# Y-babies_ATtiny84_v07.net
KiCad netlist of a schematic drawn in EAGLE
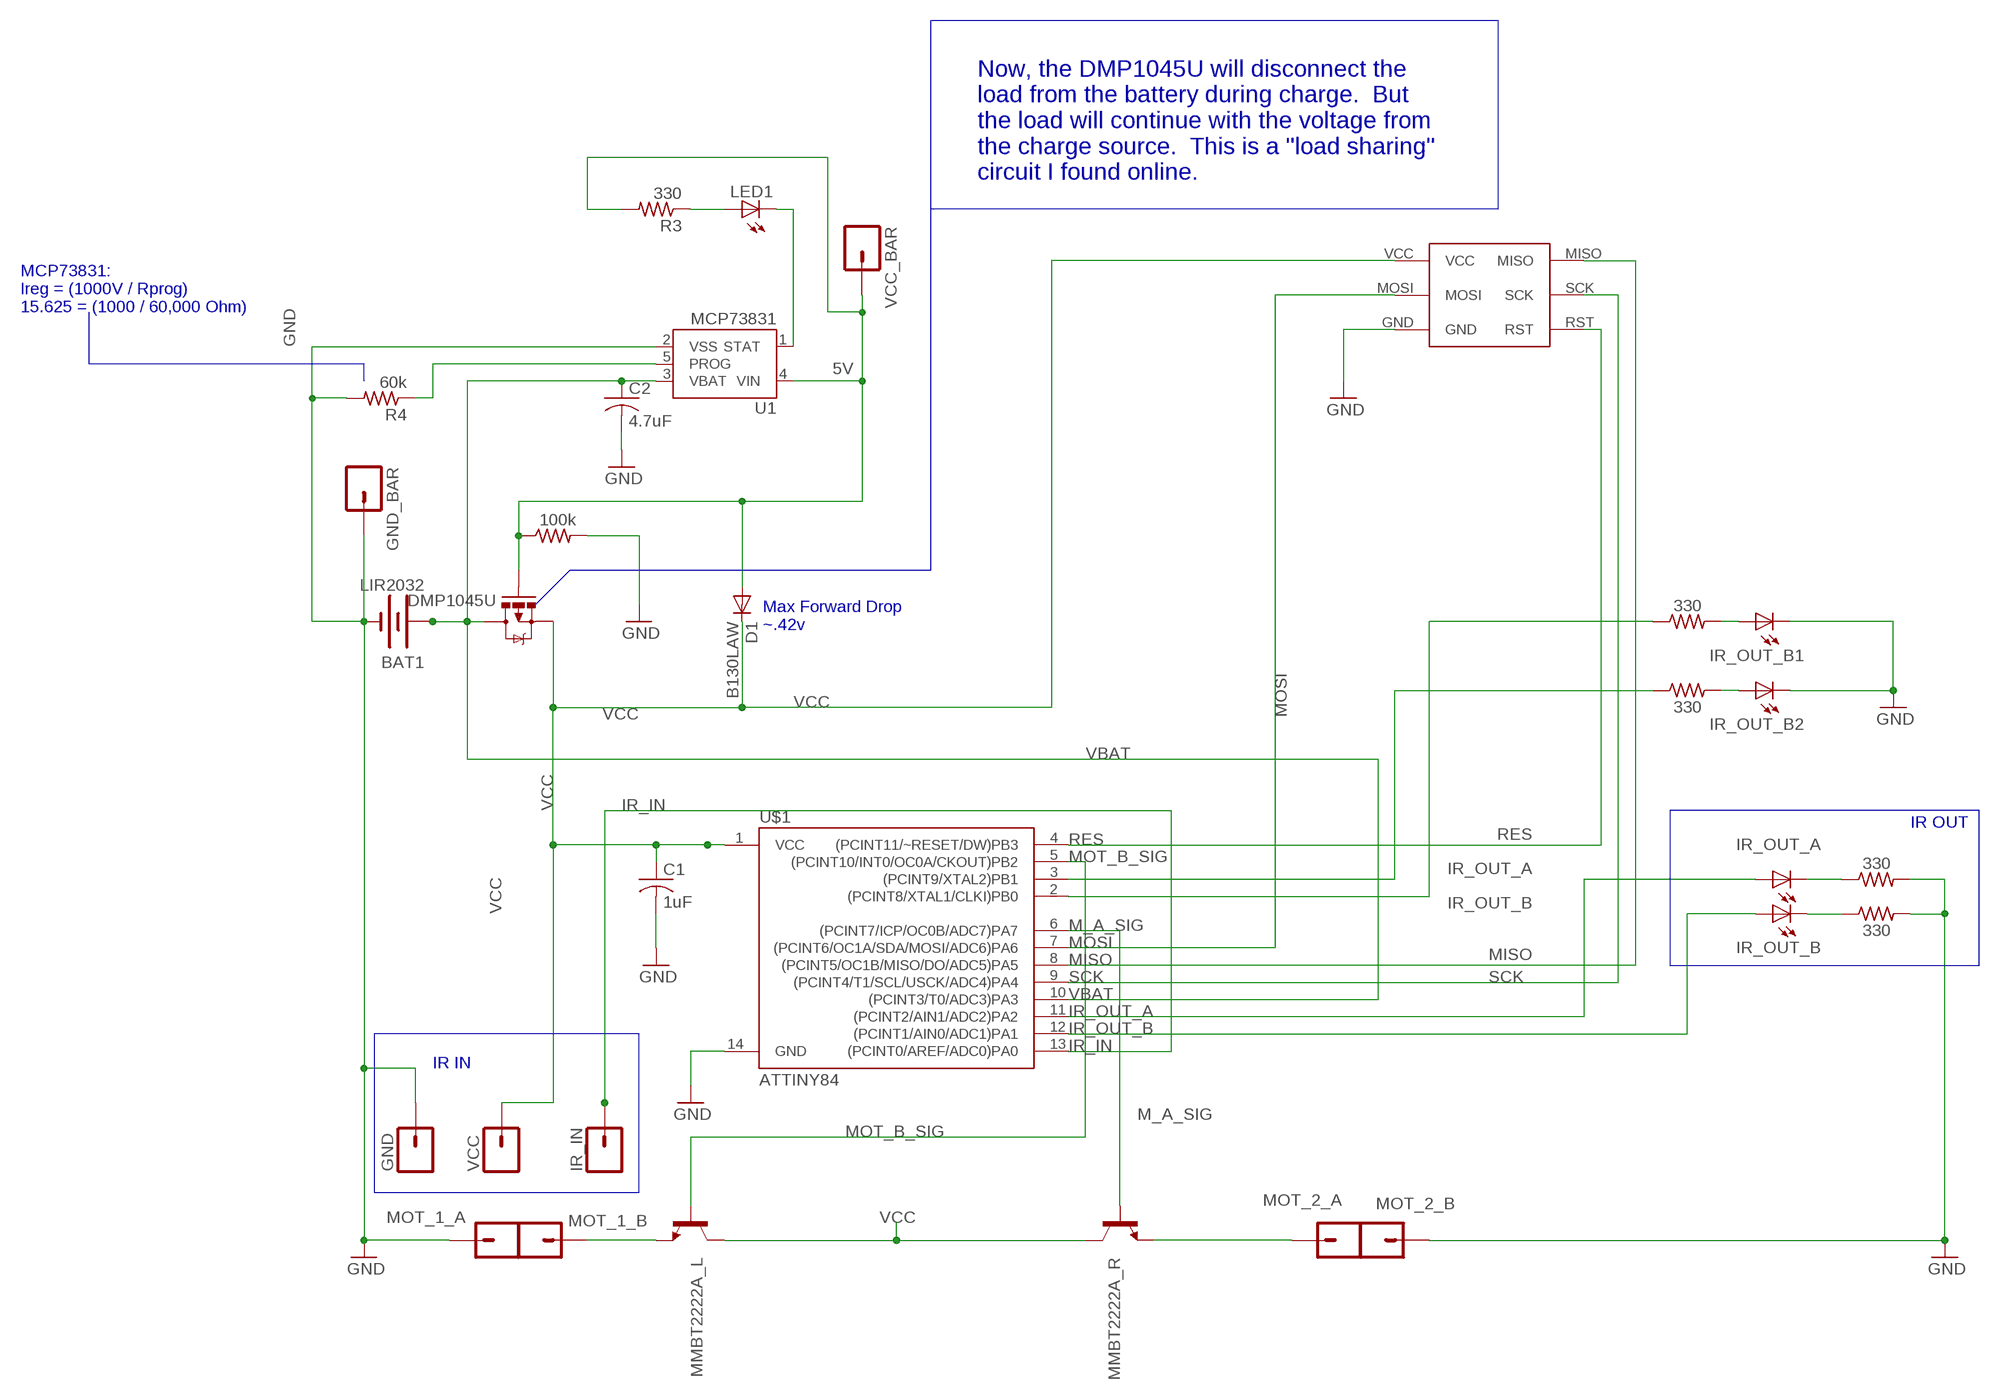
[diagram p0: schematic, sheet 1]

(export (version "E")
  (design (tool "Eeschema 10.0.6"))
  (components
    (comp (ref "BAT1")
      (value "LIR2032")
      (footprint "eagle-import:BATTCOM_20MM_PTH")
      (libsource (lib "eagle-import") (part "BATTERY20PTH"))
    )
    (comp (ref "C1")
      (value "1uF")
      (footprint "eagle-import:C0402K")
      (libsource (lib "eagle-import") (part "C-USC0402K"))
    )
    (comp (ref "C2")
      (value "4.7uF")
      (footprint "eagle-import:C0805K")
      (libsource (lib "eagle-import") (part "C-USC0805K"))
    )
    (comp (ref "D1")
      (value "B130LAW")
      (footprint "eagle-import:SOD123")
      (libsource (lib "eagle-import") (part "DIODE-SOD123"))
    )
    (comp (ref "DMP1045U")
      (value "MOSFET-PCHANNELSMD")
      (footprint "eagle-import:SOT23-3")
      (libsource (lib "eagle-import") (part "MOSFET-PCHANNELSMD"))
    )
    (comp (ref "GND")
      (value "M01PTH")
      (footprint "eagle-import:1X01")
      (libsource (lib "eagle-import") (part "M01PTH"))
    )
    (comp (ref "GND_BAR")
      (value "M01PTH")
      (footprint "eagle-import:1X01")
      (libsource (lib "eagle-import") (part "M01PTH"))
    )
    (comp (ref "IR_IN")
      (value "M01PTH")
      (footprint "eagle-import:1X01")
      (libsource (lib "eagle-import") (part "M01PTH"))
    )
    (comp (ref "IR_OUT_A")
      (value "LED3MM")
      (footprint "eagle-import:LED3MM")
      (libsource (lib "eagle-import") (part "LED3MM"))
    )
    (comp (ref "IR_OUT_B")
      (value "LED3MM")
      (footprint "eagle-import:LED3MM")
      (libsource (lib "eagle-import") (part "LED3MM"))
    )
    (comp (ref "IR_OUT_B1")
      (value "LEDSML0603")
      (footprint "eagle-import:SML0603")
      (libsource (lib "eagle-import") (part "LEDSML0603"))
    )
    (comp (ref "IR_OUT_B2")
      (value "LEDSML0603")
      (footprint "eagle-import:SML0603")
      (libsource (lib "eagle-import") (part "LEDSML0603"))
    )
    (comp (ref "LED1")
      (value "LEDSML0603")
      (footprint "eagle-import:SML0603")
      (libsource (lib "eagle-import") (part "LEDSML0603"))
    )
    (comp (ref "MMBT2222A_L")
      (value "TRANSISTOR_NPNSOT23")
      (footprint "eagle-import:SOT23")
      (libsource (lib "eagle-import") (part "TRANSISTOR_NPNSOT23"))
    )
    (comp (ref "MMBT2222A_R")
      (value "TRANSISTOR_NPNSOT23")
      (footprint "eagle-import:SOT23")
      (libsource (lib "eagle-import") (part "TRANSISTOR_NPNSOT23"))
    )
    (comp (ref "MOT_1_A")
      (value "M01SMD-4.5X1.5")
      (footprint "eagle-import:PAD-1.5X4.5")
      (libsource (lib "eagle-import") (part "M01SMD-4.5X1.5"))
    )
    (comp (ref "MOT_1_B")
      (value "M01SMD-4.5X1.5")
      (footprint "eagle-import:PAD-1.5X4.5")
      (libsource (lib "eagle-import") (part "M01SMD-4.5X1.5"))
    )
    (comp (ref "MOT_2_A")
      (value "M01SMD-4.5X1.5")
      (footprint "eagle-import:PAD-1.5X4.5")
      (libsource (lib "eagle-import") (part "M01SMD-4.5X1.5"))
    )
    (comp (ref "MOT_2_B")
      (value "M01SMD-4.5X1.5")
      (footprint "eagle-import:PAD-1.5X4.5")
      (libsource (lib "eagle-import") (part "M01SMD-4.5X1.5"))
    )
    (comp (ref "R1")
      (value "330")
      (footprint "eagle-import:R0402")
      (libsource (lib "eagle-import") (part "R-US_R0402"))
    )
    (comp (ref "R2")
      (value "330")
      (footprint "eagle-import:R0402")
      (libsource (lib "eagle-import") (part "R-US_R0402"))
    )
    (comp (ref "R3")
      (value "330")
      (footprint "eagle-import:R0402")
      (libsource (lib "eagle-import") (part "R-US_R0402"))
    )
    (comp (ref "R4")
      (value "60k")
      (footprint "eagle-import:R0402")
      (libsource (lib "eagle-import") (part "R-US_R0402"))
    )
    (comp (ref "R5")
      (value "100k")
      (footprint "eagle-import:R0402")
      (libsource (lib "eagle-import") (part "R-US_R0402"))
    )
    (comp (ref "R6")
      (value "330")
      (footprint "eagle-import:R0402")
      (libsource (lib "eagle-import") (part "R-US_R0402"))
    )
    (comp (ref "R7")
      (value "330")
      (footprint "eagle-import:R0402")
      (libsource (lib "eagle-import") (part "R-US_R0402"))
    )
    (comp (ref "U$1")
      (value "ATTINY84")
      (footprint "eagle-import:SO14")
      (libsource (lib "eagle-import") (part "ATTINY84"))
    )
    (comp (ref "U$2")
      (value "POGO_PIN_SPI_PAD")
      (footprint "eagle-import:POGO_PIN_SPI_PAD")
      (libsource (lib "eagle-import") (part "POGO_PIN_SPI_PAD"))
    )
    (comp (ref "U1")
      (value "MCP73831")
      (footprint "eagle-import:SOT23-5")
      (libsource (lib "eagle-import") (part "MCP73831"))
    )
    (comp (ref "VCC")
      (value "M01PTH")
      (footprint "eagle-import:1X01")
      (libsource (lib "eagle-import") (part "M01PTH"))
    )
    (comp (ref "VCC_BAR")
      (value "M01PTH")
      (footprint "eagle-import:1X01")
      (libsource (lib "eagle-import") (part "M01PTH"))
    )
  )
  (nets
    (net (code "1") (name "/5V") (class "Default")
      (node (ref "D1") (pin "A") (pinfunction "A_A") (pintype "passive"))
      (node (ref "DMP1045U") (pin "1") (pinfunction "G_1") (pintype "passive"))
      (node (ref "R3") (pin "2") (pinfunction "2_2") (pintype "passive"))
      (node (ref "R5") (pin "1") (pinfunction "1_1") (pintype "passive"))
      (node (ref "U1") (pin "4") (pinfunction "VIN_4") (pintype "power_in"))
      (node (ref "VCC_BAR") (pin "1") (pinfunction "1_1") (pintype "passive"))
    )
    (net (code "2") (name "/IR_IN") (class "Default")
      (node (ref "IR_IN") (pin "1") (pinfunction "1_1") (pintype "passive"))
      (node (ref "U$1") (pin "13") (pinfunction "(PCINT0/AREF/ADC0)PA0_13") (pintype "bidirectional"))
    )
    (net (code "3") (name "/IR_OUT_A") (class "Default")
      (node (ref "IR_OUT_A") (pin "A") (pinfunction "A_A") (pintype "passive"))
      (node (ref "U$1") (pin "11") (pinfunction "(PCINT2/AIN1/ADC2)PA2_11") (pintype "bidirectional"))
    )
    (net (code "4") (name "/IR_OUT_B") (class "Default")
      (node (ref "IR_OUT_B") (pin "A") (pinfunction "A_A") (pintype "passive"))
      (node (ref "U$1") (pin "12") (pinfunction "(PCINT1/AIN0/ADC1)PA1_12") (pintype "bidirectional"))
    )
    (net (code "5") (name "/MISO") (class "Default")
      (node (ref "U$1") (pin "8") (pinfunction "(PCINT5/OC1B/MISO/DO/ADC5)PA5_8") (pintype "bidirectional"))
      (node (ref "U$2") (pin "MISO") (pinfunction "MISO_MISO") (pintype "bidirectional"))
    )
    (net (code "6") (name "/MOSI") (class "Default")
      (node (ref "U$1") (pin "7") (pinfunction "(PCINT6/OC1A/SDA/MOSI/ADC6)PA6_7") (pintype "bidirectional"))
      (node (ref "U$2") (pin "MOSI") (pinfunction "MOSI_MOSI") (pintype "bidirectional"))
    )
    (net (code "7") (name "/MOT_B_SIG") (class "Default")
      (node (ref "MMBT2222A_L") (pin "1") (pinfunction "B_1") (pintype "passive"))
      (node (ref "U$1") (pin "5") (pinfunction "(PCINT10/INT0/OC0A/CKOUT)PB2_5") (pintype "bidirectional"))
    )
    (net (code "8") (name "/M_A_SIG") (class "Default")
      (node (ref "MMBT2222A_R") (pin "1") (pinfunction "B_1") (pintype "passive"))
      (node (ref "U$1") (pin "6") (pinfunction "(PCINT7/ICP/OC0B/ADC7)PA7_6") (pintype "bidirectional"))
    )
    (net (code "9") (name "/RES") (class "Default")
      (node (ref "U$1") (pin "4") (pinfunction "(PCINT11/~{RESET/DW})PB3_4") (pintype "bidirectional"))
      (node (ref "U$2") (pin "RST") (pinfunction "RST_RST") (pintype "bidirectional"))
    )
    (net (code "10") (name "/SCK") (class "Default")
      (node (ref "U$1") (pin "9") (pinfunction "(PCINT4/T1/SCL/USCK/ADC4)PA4_9") (pintype "bidirectional"))
      (node (ref "U$2") (pin "SCK") (pinfunction "SCK_SCK") (pintype "bidirectional"))
    )
    (net (code "11") (name "/VBAT") (class "Default")
      (node (ref "BAT1") (pin "1") (pinfunction "+_1") (pintype "power_in"))
      (node (ref "C2") (pin "1") (pinfunction "1_1") (pintype "passive"))
      (node (ref "DMP1045U") (pin "3") (pinfunction "D_3") (pintype "passive"))
      (node (ref "U$1") (pin "10") (pinfunction "(PCINT3/T0/ADC3)PA3_10") (pintype "bidirectional"))
      (node (ref "U1") (pin "3") (pinfunction "VBAT_3") (pintype "power_in"))
    )
    (net (code "12") (name "/VCC") (class "Default")
      (node (ref "C1") (pin "1") (pinfunction "1_1") (pintype "passive"))
      (node (ref "D1") (pin "C") (pinfunction "C_C") (pintype "passive"))
      (node (ref "DMP1045U") (pin "2") (pinfunction "S_2") (pintype "passive"))
      (node (ref "MMBT2222A_L") (pin "3") (pinfunction "C_3") (pintype "passive"))
      (node (ref "MMBT2222A_R") (pin "3") (pinfunction "C_3") (pintype "passive"))
      (node (ref "U$1") (pin "1") (pinfunction "VCC_1") (pintype "bidirectional"))
      (node (ref "U$2") (pin "VCC") (pinfunction "VCC_VCC") (pintype "bidirectional"))
      (node (ref "VCC") (pin "1") (pinfunction "1_1") (pintype "passive"))
    )
    (net (code "13") (name "GND") (class "Default")
      (node (ref "BAT1") (pin "2") (pinfunction "-_2") (pintype "power_in"))
      (node (ref "C1") (pin "2") (pinfunction "2_2") (pintype "passive"))
      (node (ref "C2") (pin "2") (pinfunction "2_2") (pintype "passive"))
      (node (ref "GND") (pin "1") (pinfunction "1_1") (pintype "passive"))
      (node (ref "GND_BAR") (pin "1") (pinfunction "1_1") (pintype "passive"))
      (node (ref "IR_OUT_B1") (pin "C") (pinfunction "C_C") (pintype "passive"))
      (node (ref "IR_OUT_B2") (pin "C") (pinfunction "C_C") (pintype "passive"))
      (node (ref "MOT_1_A") (pin "P$1") (pinfunction "1_P$1") (pintype "passive"))
      (node (ref "MOT_2_B") (pin "P$1") (pinfunction "1_P$1") (pintype "passive"))
      (node (ref "R1") (pin "2") (pinfunction "2_2") (pintype "passive"))
      (node (ref "R2") (pin "2") (pinfunction "2_2") (pintype "passive"))
      (node (ref "R4") (pin "2") (pinfunction "2_2") (pintype "passive"))
      (node (ref "R5") (pin "2") (pinfunction "2_2") (pintype "passive"))
      (node (ref "U$1") (pin "14") (pinfunction "GND_14") (pintype "bidirectional"))
      (node (ref "U$2") (pin "GND") (pinfunction "GND_GND") (pintype "bidirectional"))
      (node (ref "U1") (pin "2") (pinfunction "VSS_2") (pintype "power_in"))
    )
    (net (code "14") (name "Net-(IR_OUT_A-C)") (class "Default")
      (node (ref "IR_OUT_A") (pin "K") (pinfunction "C_K") (pintype "passive"))
      (node (ref "R1") (pin "1") (pinfunction "1_1") (pintype "passive"))
    )
    (net (code "15") (name "Net-(IR_OUT_B-C)") (class "Default")
      (node (ref "IR_OUT_B") (pin "K") (pinfunction "C_K") (pintype "passive"))
      (node (ref "R2") (pin "1") (pinfunction "1_1") (pintype "passive"))
    )
    (net (code "16") (name "Net-(IR_OUT_B1-PadA)") (class "Default")
      (node (ref "IR_OUT_B1") (pin "A") (pinfunction "A_A") (pintype "passive"))
      (node (ref "R7") (pin "2") (pinfunction "2_2") (pintype "passive"))
    )
    (net (code "17") (name "Net-(IR_OUT_B2-PadA)") (class "Default")
      (node (ref "IR_OUT_B2") (pin "A") (pinfunction "A_A") (pintype "passive"))
      (node (ref "R6") (pin "2") (pinfunction "2_2") (pintype "passive"))
    )
    (net (code "18") (name "Net-(LED1-PadA)") (class "Default")
      (node (ref "LED1") (pin "A") (pinfunction "A_A") (pintype "passive"))
      (node (ref "R3") (pin "1") (pinfunction "1_1") (pintype "passive"))
    )
    (net (code "19") (name "Net-(MMBT2222A_L-E)") (class "Default")
      (node (ref "MMBT2222A_L") (pin "2") (pinfunction "E_2") (pintype "passive"))
      (node (ref "MOT_1_B") (pin "P$1") (pinfunction "1_P$1") (pintype "passive"))
    )
    (net (code "20") (name "Net-(MMBT2222A_R-E)") (class "Default")
      (node (ref "MMBT2222A_R") (pin "2") (pinfunction "E_2") (pintype "passive"))
      (node (ref "MOT_2_A") (pin "P$1") (pinfunction "1_P$1") (pintype "passive"))
    )
    (net (code "21") (name "Net-(U$1-(PCINT8{slash}XTAL1{slash}CLKI)PB0)") (class "Default")
      (node (ref "R7") (pin "1") (pinfunction "1_1") (pintype "passive"))
      (node (ref "U$1") (pin "2") (pinfunction "(PCINT8/XTAL1/CLKI)PB0_2") (pintype "bidirectional"))
    )
    (net (code "22") (name "Net-(U$1-(PCINT9{slash}XTAL2)PB1)") (class "Default")
      (node (ref "R6") (pin "1") (pinfunction "1_1") (pintype "passive"))
      (node (ref "U$1") (pin "3") (pinfunction "(PCINT9/XTAL2)PB1_3") (pintype "bidirectional"))
    )
    (net (code "23") (name "Net-(U1-PROG)") (class "Default")
      (node (ref "R4") (pin "1") (pinfunction "1_1") (pintype "passive"))
      (node (ref "U1") (pin "5") (pinfunction "PROG_5") (pintype "input"))
    )
    (net (code "24") (name "Net-(U1-STAT)") (class "Default")
      (node (ref "LED1") (pin "C") (pinfunction "C_C") (pintype "passive"))
      (node (ref "U1") (pin "1") (pinfunction "STAT_1") (pintype "output"))
    )
  )
)
